# Motor_Controller.net
KiCad netlist of a schematic drawn in Altium Designer
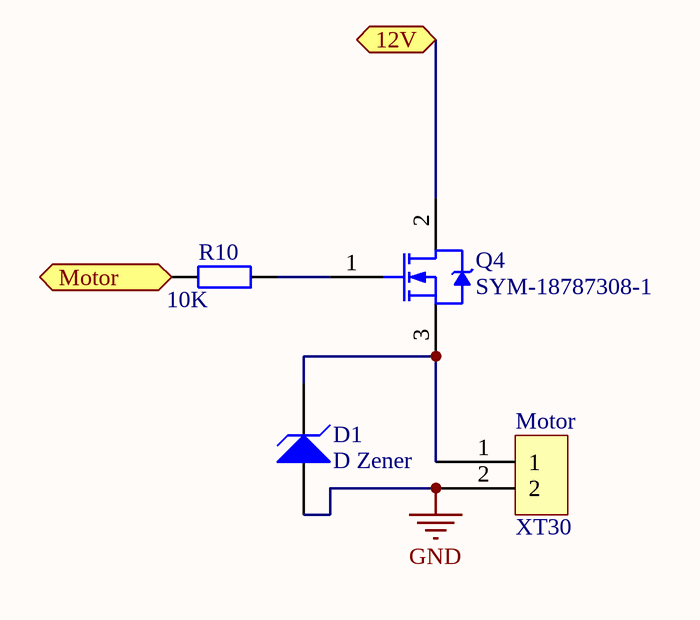
[diagram p0: Motor_Controller.SchDoc]

(export (version "E")
  (design (tool "Eeschema 10.0.6"))
  (components
    (comp (ref "D1")
      (value "D Zener")
      (footprint "PCB-l9es7xv56lx35n1ll0aq-1")
      (description "1N4745A Series 1.3 W 16 V 200 mA 5 % Tolerance Through Hole Zener Diode - DO-41")
      (fields (field (name "MANUFACTURER PART NUMBER") "1N4745A-TR"))
      (libsource (lib "CommunityVault") (part "SYM-88cd428957ea570a-1"))
    )
    (comp (ref "Motor")
      (value "XT30")
      (footprint "PCB-8h6goupi0sbkduz6cbnu-1")
      (description "Very similar to the XT60 models, but smaller and made for 30A")
      (libsource (lib "CommunityVault") (part "CMP-nlx8yci0umf6n9sk0ty3-1"))
    )
    (comp (ref "Q4")
      (value "SYM-18787308-1")
      (footprint "PCB-18787308-1")
      (description "MS")
      (libsource (lib "CommunityVault") (part "SYM-18787308-1"))
    )
    (comp (ref "R10")
      (value "Res2")
      (footprint "PCB-mctr3h3tvednl0z90ud0-1")
      (description "Resistor; Carbon Composition; Res 3.9 Kilohms; Pwr-Rtg 0.25 W; Tol 5%; Axial")
      (fields (field (name "MANUFACTURER PART NUMBER") "OD392JE") (field (name "OHMS") "10K"))
      (libsource (lib "CommunityVault") (part "CMP-1413dd18cda2cbd4-1"))
    )
  )
  (nets
    (net (code "1") (name "/12V") (class "Default")
      (node (ref "Q4") (pin "2") (pinfunction "D_2") (pintype "passive"))
    )
    (net (code "2") (name "/Motor") (class "Default")
      (node (ref "R10") (pin "1") (pinfunction "1_1") (pintype "passive"))
    )
    (net (code "3") (name "GND") (class "Default")
      (node (ref "D1") (pin "1") (pinfunction "A_1") (pintype "passive"))
      (node (ref "Motor") (pin "2") (pinfunction "2_2") (pintype "passive"))
    )
    (net (code "4") (name "Net-(D1-K)") (class "Default")
      (node (ref "D1") (pin "2") (pinfunction "K_2") (pintype "passive"))
      (node (ref "Motor") (pin "1") (pinfunction "1_1") (pintype "passive"))
      (node (ref "Q4") (pin "3") (pinfunction "S_3") (pintype "passive"))
    )
    (net (code "5") (name "Net-(Q4-G)") (class "Default")
      (node (ref "Q4") (pin "1") (pinfunction "G_1") (pintype "passive"))
      (node (ref "R10") (pin "2") (pinfunction "2_2") (pintype "passive"))
    )
  )
)
